# TelemetryBoard.net
KiCad netlist of a schematic drawn in Altium Designer
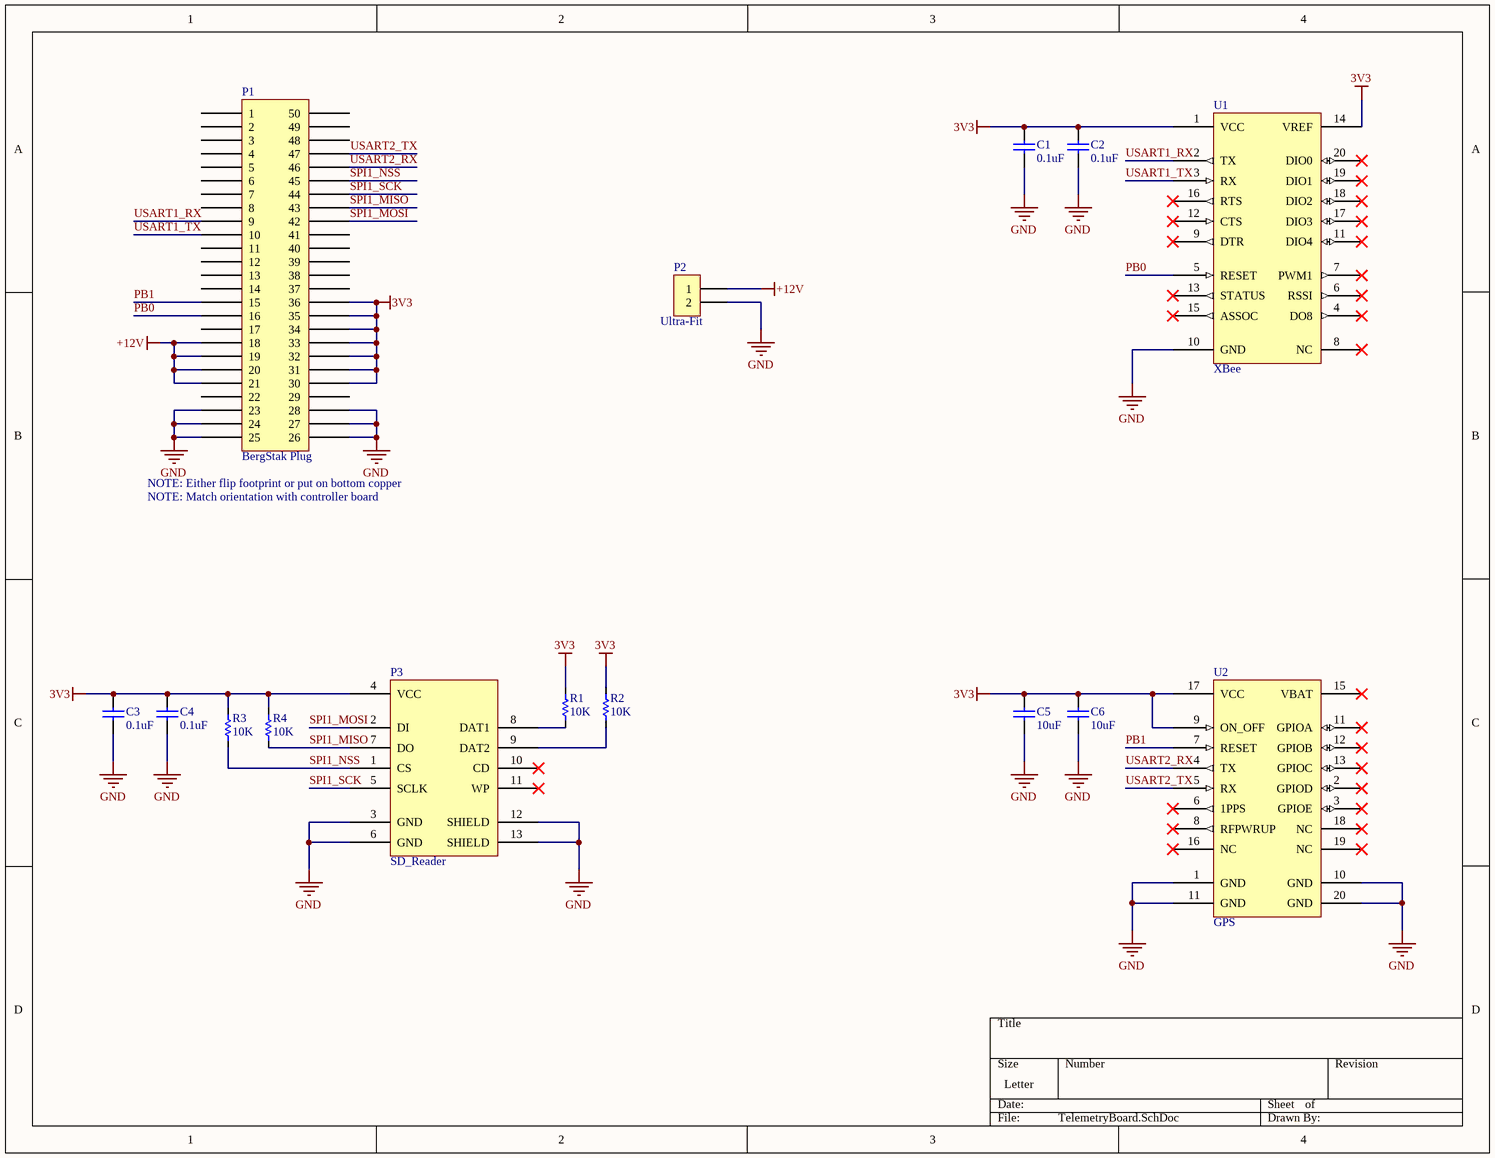
[diagram p0: TelemetryBoard.SchDoc]

(export (version "E")
  (design (tool "Eeschema 10.0.6"))
  (components
    (comp (ref "C1")
      (value "0.1uF")
      (footprint "0603")
      (description "0.10µF ±10% 50V Ceramic Capacitor X7R 0603 (1608 Metric)")
      (fields
        (field (name "MANUFACTURER") "AVX Corporation")
        (field (name "MANUFACTURERPARTNUMBER") "06035C104KAT2A")
      )
      (libsource (lib "Schematic Diagrams") (part "CAP CER 0.1UF 50V 10% X7R 0603"))
    )
    (comp (ref "C2")
      (value "0.1uF")
      (footprint "0603")
      (description "0.10µF ±10% 50V Ceramic Capacitor X7R 0603 (1608 Metric)")
      (fields
        (field (name "MANUFACTURER") "AVX Corporation")
        (field (name "MANUFACTURERPARTNUMBER") "06035C104KAT2A")
      )
      (libsource (lib "Schematic Diagrams") (part "CAP CER 0.1UF 50V 10% X7R 0603"))
    )
    (comp (ref "C3")
      (value "0.1uF")
      (footprint "0603")
      (description "0.10µF ±10% 50V Ceramic Capacitor X7R 0603 (1608 Metric)")
      (fields
        (field (name "MANUFACTURER") "AVX Corporation")
        (field (name "MANUFACTURERPARTNUMBER") "06035C104KAT2A")
      )
      (libsource (lib "Schematic Diagrams") (part "CAP CER 0.1UF 50V 10% X7R 0603"))
    )
    (comp (ref "C4")
      (value "0.1uF")
      (footprint "0603")
      (description "0.10µF ±10% 50V Ceramic Capacitor X7R 0603 (1608 Metric)")
      (fields
        (field (name "MANUFACTURER") "AVX Corporation")
        (field (name "MANUFACTURERPARTNUMBER") "06035C104KAT2A")
      )
      (libsource (lib "Schematic Diagrams") (part "CAP CER 0.1UF 50V 10% X7R 0603"))
    )
    (comp (ref "C5")
      (value "10uF")
      (footprint "0603")
      (description "10µF ±20% 25V Ceramic Capacitor X5R 0603 (1608 Metric)")
      (fields
        (field (name "MANUFACTURER") "Murata Electronics North America")
        (field (name "MANUFACTURERPARTNUMBER") "GRM188R61E106MA73D")
      )
      (libsource (lib "Schematic Diagrams") (part "CAP CER 10uF 25V 20% X5R 0603"))
    )
    (comp (ref "C6")
      (value "10uF")
      (footprint "0603")
      (description "10µF ±20% 25V Ceramic Capacitor X5R 0603 (1608 Metric)")
      (fields
        (field (name "MANUFACTURER") "Murata Electronics North America")
        (field (name "MANUFACTURERPARTNUMBER") "GRM188R61E106MA73D")
      )
      (libsource (lib "Schematic Diagrams") (part "CAP CER 10uF 25V 20% X5R 0603"))
    )
    (comp (ref "P1")
      (value "BergStak Plug")
      (footprint "609-5226-1-ND")
      (description "50 Position Connector Plug, Outer Shroud Contacts Surface Mount Gold")
      (libsource (lib "Schematic Diagrams") (part "BergStak 50 Position Connector Plug"))
    )
    (comp (ref "P2")
      (value "Ultra-Fit")
      (footprint "WM11673-ND")
      (description "2 Positions Header, Shrouded Connector 0.138\" (3.50mm) Through Hole Gold")
      (libsource (lib "Schematic Diagrams") (part "2 Position Ultra-Fit Connector"))
    )
    (comp (ref "P3")
      (value "SD_Reader")
      (footprint "SD_Reader")
      (libsource (lib "Schematic Diagrams") (part "SD_Reader"))
    )
    (comp (ref "R1")
      (value "10K")
      (footprint "RES_0603")
      (description "RES SMD 10K OHM 1% 1/10W 0603")
      (fields
        (field (name "MANUFACTURE PART NUMBER") "RC0603FR-0710KL")
        (field (name "VENDOR PART NUMBER") "311-10.0KHRCT-ND")
      )
      (libsource (lib "Schematic Diagrams") (part "RES SMD 10K OHM 1% 1/10W 0603"))
    )
    (comp (ref "R2")
      (value "10K")
      (footprint "RES_0603")
      (description "RES SMD 10K OHM 1% 1/10W 0603")
      (fields
        (field (name "MANUFACTURE PART NUMBER") "RC0603FR-0710KL")
        (field (name "VENDOR PART NUMBER") "311-10.0KHRCT-ND")
      )
      (libsource (lib "Schematic Diagrams") (part "RES SMD 10K OHM 1% 1/10W 0603"))
    )
    (comp (ref "R3")
      (value "10K")
      (footprint "RES_0603")
      (description "RES SMD 10K OHM 1% 1/10W 0603")
      (fields
        (field (name "MANUFACTURE PART NUMBER") "RC0603FR-0710KL")
        (field (name "VENDOR PART NUMBER") "311-10.0KHRCT-ND")
      )
      (libsource (lib "Schematic Diagrams") (part "RES SMD 10K OHM 1% 1/10W 0603"))
    )
    (comp (ref "R4")
      (value "10K")
      (footprint "RES_0603")
      (description "RES SMD 10K OHM 1% 1/10W 0603")
      (fields
        (field (name "MANUFACTURE PART NUMBER") "RC0603FR-0710KL")
        (field (name "VENDOR PART NUMBER") "311-10.0KHRCT-ND")
      )
      (libsource (lib "Schematic Diagrams") (part "RES SMD 10K OHM 1% 1/10W 0603"))
    )
    (comp (ref "U1")
      (value "XBee")
      (footprint "XBee-PRO")
      (libsource (lib "Schematic Diagrams") (part "XBee"))
    )
    (comp (ref "U2")
      (value "GPS")
      (footprint "EVM-GPS-F4")
      (description "GPS Module")
      (libsource (lib "Schematic Diagrams") (part "GPS"))
    )
  )
  (nets
    (net (code "1") (name "+12V") (class "Default")
      (node (ref "P1") (pin "18") (pinfunction "18_18") (pintype "passive"))
      (node (ref "P1") (pin "19") (pinfunction "19_19") (pintype "passive"))
      (node (ref "P1") (pin "20") (pinfunction "20_20") (pintype "passive"))
      (node (ref "P1") (pin "21") (pinfunction "21_21") (pintype "passive"))
      (node (ref "P2") (pin "1") (pinfunction "1_1") (pintype "passive"))
    )
    (net (code "2") (name "/PB0") (class "Default")
      (node (ref "P1") (pin "16") (pinfunction "16_16") (pintype "passive"))
      (node (ref "U1") (pin "5") (pinfunction "RESET_5") (pintype "input"))
    )
    (net (code "3") (name "/PB1") (class "Default")
      (node (ref "P1") (pin "15") (pinfunction "15_15") (pintype "passive"))
      (node (ref "U2") (pin "7") (pinfunction "RESET_7") (pintype "input"))
    )
    (net (code "4") (name "/SPI1_MISO") (class "Default")
      (node (ref "P1") (pin "43") (pinfunction "43_43") (pintype "passive"))
      (node (ref "P3") (pin "7") (pinfunction "DO_7") (pintype "passive"))
      (node (ref "R4") (pin "1") (pinfunction "1_1") (pintype "passive"))
    )
    (net (code "5") (name "/SPI1_MOSI") (class "Default")
      (node (ref "P1") (pin "42") (pinfunction "42_42") (pintype "passive"))
      (node (ref "P3") (pin "2") (pinfunction "DI_2") (pintype "passive"))
    )
    (net (code "6") (name "/SPI1_NSS") (class "Default")
      (node (ref "P1") (pin "45") (pinfunction "45_45") (pintype "passive"))
      (node (ref "P3") (pin "1") (pinfunction "CS_1") (pintype "passive"))
      (node (ref "R3") (pin "1") (pinfunction "1_1") (pintype "passive"))
    )
    (net (code "7") (name "/SPI1_SCK") (class "Default")
      (node (ref "P1") (pin "44") (pinfunction "44_44") (pintype "passive"))
      (node (ref "P3") (pin "5") (pinfunction "SCLK_5") (pintype "passive"))
    )
    (net (code "8") (name "/USART1_RX") (class "Default")
      (node (ref "P1") (pin "9") (pinfunction "9_9") (pintype "passive"))
      (node (ref "U1") (pin "2") (pinfunction "TX_2") (pintype "output"))
    )
    (net (code "9") (name "/USART1_TX") (class "Default")
      (node (ref "P1") (pin "10") (pinfunction "10_10") (pintype "passive"))
      (node (ref "U1") (pin "3") (pinfunction "RX_3") (pintype "input"))
    )
    (net (code "10") (name "/USART2_RX") (class "Default")
      (node (ref "P1") (pin "46") (pinfunction "46_46") (pintype "passive"))
      (node (ref "U2") (pin "4") (pinfunction "TX_4") (pintype "output"))
    )
    (net (code "11") (name "/USART2_TX") (class "Default")
      (node (ref "P1") (pin "47") (pinfunction "47_47") (pintype "passive"))
      (node (ref "U2") (pin "5") (pinfunction "RX_5") (pintype "input"))
    )
    (net (code "12") (name "3V3") (class "Default")
      (node (ref "C1") (pin "2") (pinfunction "2_2") (pintype "passive"))
      (node (ref "C2") (pin "2") (pinfunction "2_2") (pintype "passive"))
      (node (ref "C3") (pin "2") (pinfunction "2_2") (pintype "passive"))
      (node (ref "C4") (pin "2") (pinfunction "2_2") (pintype "passive"))
      (node (ref "C5") (pin "2") (pinfunction "2_2") (pintype "passive"))
      (node (ref "C6") (pin "2") (pinfunction "2_2") (pintype "passive"))
      (node (ref "P1") (pin "30") (pinfunction "30_30") (pintype "passive"))
      (node (ref "P1") (pin "31") (pinfunction "31_31") (pintype "passive"))
      (node (ref "P1") (pin "32") (pinfunction "32_32") (pintype "passive"))
      (node (ref "P1") (pin "33") (pinfunction "33_33") (pintype "passive"))
      (node (ref "P1") (pin "34") (pinfunction "34_34") (pintype "passive"))
      (node (ref "P1") (pin "35") (pinfunction "35_35") (pintype "passive"))
      (node (ref "P1") (pin "36") (pinfunction "36_36") (pintype "passive"))
      (node (ref "P3") (pin "4") (pinfunction "VCC_4") (pintype "power_in"))
      (node (ref "R1") (pin "2") (pinfunction "2_2") (pintype "passive"))
      (node (ref "R2") (pin "2") (pinfunction "2_2") (pintype "passive"))
      (node (ref "R3") (pin "2") (pinfunction "2_2") (pintype "passive"))
      (node (ref "R4") (pin "2") (pinfunction "2_2") (pintype "passive"))
      (node (ref "U1") (pin "1") (pinfunction "VCC_1") (pintype "power_in"))
      (node (ref "U1") (pin "14") (pinfunction "VREF_14") (pintype "power_in"))
      (node (ref "U2") (pin "17") (pinfunction "VCC_17") (pintype "power_in"))
      (node (ref "U2") (pin "9") (pinfunction "ON_OFF_9") (pintype "input"))
    )
    (net (code "13") (name "GND") (class "Default")
      (node (ref "C1") (pin "1") (pinfunction "1_1") (pintype "passive"))
      (node (ref "C2") (pin "1") (pinfunction "1_1") (pintype "passive"))
      (node (ref "C3") (pin "1") (pinfunction "1_1") (pintype "passive"))
      (node (ref "C4") (pin "1") (pinfunction "1_1") (pintype "passive"))
      (node (ref "C5") (pin "1") (pinfunction "1_1") (pintype "passive"))
      (node (ref "C6") (pin "1") (pinfunction "1_1") (pintype "passive"))
      (node (ref "P1") (pin "23") (pinfunction "23_23") (pintype "passive"))
      (node (ref "P1") (pin "24") (pinfunction "24_24") (pintype "passive"))
      (node (ref "P1") (pin "25") (pinfunction "25_25") (pintype "passive"))
      (node (ref "P1") (pin "26") (pinfunction "26_26") (pintype "passive"))
      (node (ref "P1") (pin "27") (pinfunction "27_27") (pintype "passive"))
      (node (ref "P1") (pin "28") (pinfunction "28_28") (pintype "passive"))
      (node (ref "P2") (pin "2") (pinfunction "2_2") (pintype "passive"))
      (node (ref "P3") (pin "12") (pinfunction "SHIELD_12") (pintype "passive"))
      (node (ref "P3") (pin "13") (pinfunction "SHIELD_13") (pintype "passive"))
      (node (ref "P3") (pin "3") (pinfunction "GND_3") (pintype "power_in"))
      (node (ref "P3") (pin "6") (pinfunction "GND_6") (pintype "power_in"))
      (node (ref "U1") (pin "10") (pinfunction "GND_10") (pintype "passive"))
      (node (ref "U2") (pin "1") (pinfunction "GND_1") (pintype "power_in"))
      (node (ref "U2") (pin "10") (pinfunction "GND_10") (pintype "power_in"))
      (node (ref "U2") (pin "11") (pinfunction "GND_11") (pintype "power_in"))
      (node (ref "U2") (pin "20") (pinfunction "GND_20") (pintype "power_in"))
    )
    (net (code "14") (name "Net-(P3-DAT1)") (class "Default")
      (node (ref "P3") (pin "8") (pinfunction "DAT1_8") (pintype "passive"))
      (node (ref "R1") (pin "1") (pinfunction "1_1") (pintype "passive"))
    )
    (net (code "15") (name "Net-(P3-DAT2)") (class "Default")
      (node (ref "P3") (pin "9") (pinfunction "DAT2_9") (pintype "passive"))
      (node (ref "R2") (pin "1") (pinfunction "1_1") (pintype "passive"))
    )
    (net (code "16") (name "unconnected-(P1-Pad1)") (class "Default")
      (node (ref "P1") (pin "1") (pinfunction "1_1") (pintype "passive"))
    )
    (net (code "17") (name "unconnected-(P1-Pad2)") (class "Default")
      (node (ref "P1") (pin "2") (pinfunction "2_2") (pintype "passive"))
    )
    (net (code "18") (name "unconnected-(P1-Pad3)") (class "Default")
      (node (ref "P1") (pin "3") (pinfunction "3_3") (pintype "passive"))
    )
    (net (code "19") (name "unconnected-(P1-Pad4)") (class "Default")
      (node (ref "P1") (pin "4") (pinfunction "4_4") (pintype "passive"))
    )
    (net (code "20") (name "unconnected-(P1-Pad5)") (class "Default")
      (node (ref "P1") (pin "5") (pinfunction "5_5") (pintype "passive"))
    )
    (net (code "21") (name "unconnected-(P1-Pad6)") (class "Default")
      (node (ref "P1") (pin "6") (pinfunction "6_6") (pintype "passive"))
    )
    (net (code "22") (name "unconnected-(P1-Pad7)") (class "Default")
      (node (ref "P1") (pin "7") (pinfunction "7_7") (pintype "passive"))
    )
    (net (code "23") (name "unconnected-(P1-Pad8)") (class "Default")
      (node (ref "P1") (pin "8") (pinfunction "8_8") (pintype "passive"))
    )
    (net (code "24") (name "unconnected-(P1-Pad11)") (class "Default")
      (node (ref "P1") (pin "11") (pinfunction "11_11") (pintype "passive"))
    )
    (net (code "25") (name "unconnected-(P1-Pad12)") (class "Default")
      (node (ref "P1") (pin "12") (pinfunction "12_12") (pintype "passive"))
    )
    (net (code "26") (name "unconnected-(P1-Pad13)") (class "Default")
      (node (ref "P1") (pin "13") (pinfunction "13_13") (pintype "passive"))
    )
    (net (code "27") (name "unconnected-(P1-Pad14)") (class "Default")
      (node (ref "P1") (pin "14") (pinfunction "14_14") (pintype "passive"))
    )
    (net (code "28") (name "unconnected-(P1-Pad17)") (class "Default")
      (node (ref "P1") (pin "17") (pinfunction "17_17") (pintype "passive"))
    )
    (net (code "29") (name "unconnected-(P1-Pad22)") (class "Default")
      (node (ref "P1") (pin "22") (pinfunction "22_22") (pintype "passive"))
    )
    (net (code "30") (name "unconnected-(P1-Pad29)") (class "Default")
      (node (ref "P1") (pin "29") (pinfunction "29_29") (pintype "passive"))
    )
    (net (code "31") (name "unconnected-(P1-Pad37)") (class "Default")
      (node (ref "P1") (pin "37") (pinfunction "37_37") (pintype "passive"))
    )
    (net (code "32") (name "unconnected-(P1-Pad38)") (class "Default")
      (node (ref "P1") (pin "38") (pinfunction "38_38") (pintype "passive"))
    )
    (net (code "33") (name "unconnected-(P1-Pad39)") (class "Default")
      (node (ref "P1") (pin "39") (pinfunction "39_39") (pintype "passive"))
    )
    (net (code "34") (name "unconnected-(P1-Pad40)") (class "Default")
      (node (ref "P1") (pin "40") (pinfunction "40_40") (pintype "passive"))
    )
    (net (code "35") (name "unconnected-(P1-Pad41)") (class "Default")
      (node (ref "P1") (pin "41") (pinfunction "41_41") (pintype "passive"))
    )
    (net (code "36") (name "unconnected-(P1-Pad48)") (class "Default")
      (node (ref "P1") (pin "48") (pinfunction "48_48") (pintype "passive"))
    )
    (net (code "37") (name "unconnected-(P1-Pad49)") (class "Default")
      (node (ref "P1") (pin "49") (pinfunction "49_49") (pintype "passive"))
    )
    (net (code "38") (name "unconnected-(P1-Pad50)") (class "Default")
      (node (ref "P1") (pin "50") (pinfunction "50_50") (pintype "passive"))
    )
    (net (code "39") (name "unconnected-(P3-CD-Pad10)") (class "Default")
      (node (ref "P3") (pin "10") (pinfunction "CD_10") (pintype "passive+no_connect"))
    )
    (net (code "40") (name "unconnected-(P3-WP-Pad11)") (class "Default")
      (node (ref "P3") (pin "11") (pinfunction "WP_11") (pintype "passive+no_connect"))
    )
    (net (code "41") (name "unconnected-(U1-ASSOC-Pad15)") (class "Default")
      (node (ref "U1") (pin "15") (pinfunction "ASSOC_15") (pintype "output+no_connect"))
    )
    (net (code "42") (name "unconnected-(U1-CTS-Pad12)") (class "Default")
      (node (ref "U1") (pin "12") (pinfunction "CTS_12") (pintype "input+no_connect"))
    )
    (net (code "43") (name "unconnected-(U1-DIO0-Pad20)") (class "Default")
      (node (ref "U1") (pin "20") (pinfunction "DIO0_20") (pintype "bidirectional+no_connect"))
    )
    (net (code "44") (name "unconnected-(U1-DIO1-Pad19)") (class "Default")
      (node (ref "U1") (pin "19") (pinfunction "DIO1_19") (pintype "bidirectional+no_connect"))
    )
    (net (code "45") (name "unconnected-(U1-DIO2-Pad18)") (class "Default")
      (node (ref "U1") (pin "18") (pinfunction "DIO2_18") (pintype "bidirectional+no_connect"))
    )
    (net (code "46") (name "unconnected-(U1-DIO3-Pad17)") (class "Default")
      (node (ref "U1") (pin "17") (pinfunction "DIO3_17") (pintype "bidirectional+no_connect"))
    )
    (net (code "47") (name "unconnected-(U1-DIO4-Pad11)") (class "Default")
      (node (ref "U1") (pin "11") (pinfunction "DIO4_11") (pintype "bidirectional+no_connect"))
    )
    (net (code "48") (name "unconnected-(U1-DO8-Pad4)") (class "Default")
      (node (ref "U1") (pin "4") (pinfunction "DO8_4") (pintype "output+no_connect"))
    )
    (net (code "49") (name "unconnected-(U1-DTR-Pad9)") (class "Default")
      (node (ref "U1") (pin "9") (pinfunction "DTR_9") (pintype "output+no_connect"))
    )
    (net (code "50") (name "unconnected-(U1-NC-Pad8)") (class "Default")
      (node (ref "U1") (pin "8") (pinfunction "NC_8") (pintype "passive+no_connect"))
    )
    (net (code "51") (name "unconnected-(U1-PWM1-Pad7)") (class "Default")
      (node (ref "U1") (pin "7") (pinfunction "PWM1_7") (pintype "output+no_connect"))
    )
    (net (code "52") (name "unconnected-(U1-RSSI-Pad6)") (class "Default")
      (node (ref "U1") (pin "6") (pinfunction "RSSI_6") (pintype "output+no_connect"))
    )
    (net (code "53") (name "unconnected-(U1-RTS-Pad16)") (class "Default")
      (node (ref "U1") (pin "16") (pinfunction "RTS_16") (pintype "output+no_connect"))
    )
    (net (code "54") (name "unconnected-(U1-STATUS-Pad13)") (class "Default")
      (node (ref "U1") (pin "13") (pinfunction "STATUS_13") (pintype "output+no_connect"))
    )
    (net (code "55") (name "unconnected-(U2-1PPS-Pad6)") (class "Default")
      (node (ref "U2") (pin "6") (pinfunction "1PPS_6") (pintype "output+no_connect"))
    )
    (net (code "56") (name "unconnected-(U2-GPIOA-Pad11)") (class "Default")
      (node (ref "U2") (pin "11") (pinfunction "GPIOA_11") (pintype "bidirectional+no_connect"))
    )
    (net (code "57") (name "unconnected-(U2-GPIOB-Pad12)") (class "Default")
      (node (ref "U2") (pin "12") (pinfunction "GPIOB_12") (pintype "bidirectional+no_connect"))
    )
    (net (code "58") (name "unconnected-(U2-GPIOC-Pad13)") (class "Default")
      (node (ref "U2") (pin "13") (pinfunction "GPIOC_13") (pintype "bidirectional+no_connect"))
    )
    (net (code "59") (name "unconnected-(U2-GPIOD-Pad2)") (class "Default")
      (node (ref "U2") (pin "2") (pinfunction "GPIOD_2") (pintype "bidirectional+no_connect"))
    )
    (net (code "60") (name "unconnected-(U2-GPIOE-Pad3)") (class "Default")
      (node (ref "U2") (pin "3") (pinfunction "GPIOE_3") (pintype "bidirectional+no_connect"))
    )
    (net (code "61") (name "unconnected-(U2-NC-Pad16)") (class "Default")
      (node (ref "U2") (pin "16") (pinfunction "NC_16") (pintype "passive+no_connect"))
    )
    (net (code "62") (name "unconnected-(U2-NC-Pad18)") (class "Default")
      (node (ref "U2") (pin "18") (pinfunction "NC_18") (pintype "passive+no_connect"))
    )
    (net (code "63") (name "unconnected-(U2-NC-Pad19)") (class "Default")
      (node (ref "U2") (pin "19") (pinfunction "NC_19") (pintype "passive+no_connect"))
    )
    (net (code "64") (name "unconnected-(U2-RFPWRUP-Pad8)") (class "Default")
      (node (ref "U2") (pin "8") (pinfunction "RFPWRUP_8") (pintype "output+no_connect"))
    )
    (net (code "65") (name "unconnected-(U2-VBAT-Pad15)") (class "Default")
      (node (ref "U2") (pin "15") (pinfunction "VBAT_15") (pintype "power_in+no_connect"))
    )
  )
)
